# BadgeBoard.net
KiCad netlist of a schematic drawn in EAGLE
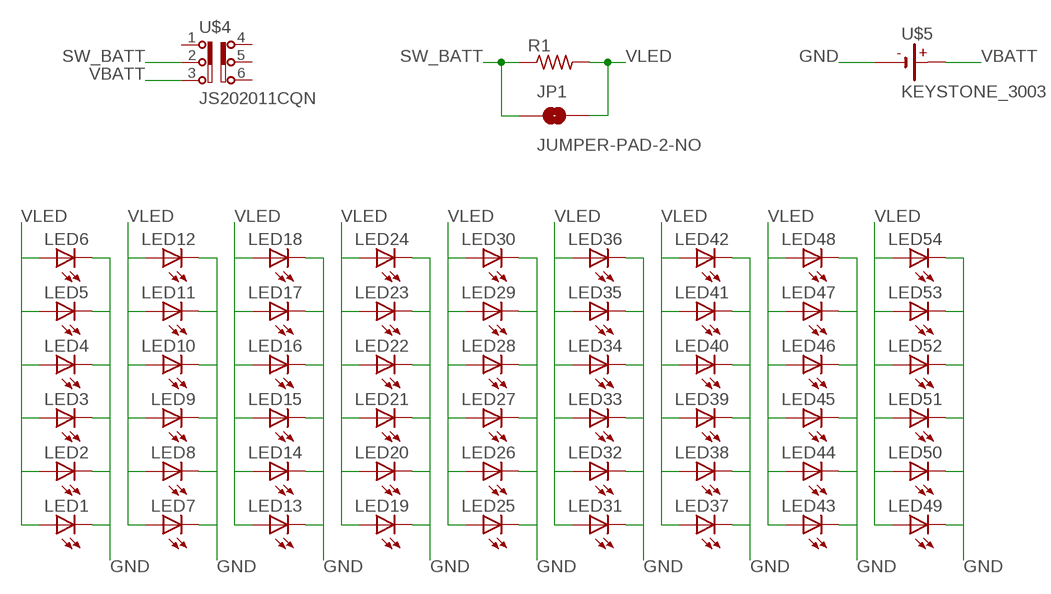
[diagram p0: schematic, sheet 1]

(export (version "E")
  (design (tool "Eeschema 10.0.6"))
  (components
    (comp (ref "JP1")
      (value "JUMPER-PAD-2-NO")
      (footprint "eagle-import:PAD-JUMPER-2-NO_NO_SILK")
      (libsource (lib "eagle-import") (part "JUMPER-PAD-2-NO"))
    )
    (comp (ref "LED1")
      (value "LED3MM")
      (footprint "eagle-import:LED3MM")
      (libsource (lib "eagle-import") (part "LED3MM"))
    )
    (comp (ref "LED2")
      (value "LED3MM")
      (footprint "eagle-import:LED3MM")
      (libsource (lib "eagle-import") (part "LED3MM"))
    )
    (comp (ref "LED3")
      (value "LED3MM")
      (footprint "eagle-import:LED3MM")
      (libsource (lib "eagle-import") (part "LED3MM"))
    )
    (comp (ref "LED4")
      (value "LED3MM")
      (footprint "eagle-import:LED3MM")
      (libsource (lib "eagle-import") (part "LED3MM"))
    )
    (comp (ref "LED5")
      (value "LED3MM")
      (footprint "eagle-import:LED3MM")
      (libsource (lib "eagle-import") (part "LED3MM"))
    )
    (comp (ref "LED6")
      (value "LED3MM")
      (footprint "eagle-import:LED3MM")
      (libsource (lib "eagle-import") (part "LED3MM"))
    )
    (comp (ref "LED7")
      (value "LED3MM")
      (footprint "eagle-import:LED3MM")
      (libsource (lib "eagle-import") (part "LED3MM"))
    )
    (comp (ref "LED8")
      (value "LED3MM")
      (footprint "eagle-import:LED3MM")
      (libsource (lib "eagle-import") (part "LED3MM"))
    )
    (comp (ref "LED9")
      (value "LED3MM")
      (footprint "eagle-import:LED3MM")
      (libsource (lib "eagle-import") (part "LED3MM"))
    )
    (comp (ref "LED10")
      (value "LED3MM")
      (footprint "eagle-import:LED3MM")
      (libsource (lib "eagle-import") (part "LED3MM"))
    )
    (comp (ref "LED11")
      (value "LED3MM")
      (footprint "eagle-import:LED3MM")
      (libsource (lib "eagle-import") (part "LED3MM"))
    )
    (comp (ref "LED12")
      (value "LED3MM")
      (footprint "eagle-import:LED3MM")
      (libsource (lib "eagle-import") (part "LED3MM"))
    )
    (comp (ref "LED13")
      (value "LED3MM")
      (footprint "eagle-import:LED3MM")
      (libsource (lib "eagle-import") (part "LED3MM"))
    )
    (comp (ref "LED14")
      (value "LED3MM")
      (footprint "eagle-import:LED3MM")
      (libsource (lib "eagle-import") (part "LED3MM"))
    )
    (comp (ref "LED15")
      (value "LED3MM")
      (footprint "eagle-import:LED3MM")
      (libsource (lib "eagle-import") (part "LED3MM"))
    )
    (comp (ref "LED16")
      (value "LED3MM")
      (footprint "eagle-import:LED3MM")
      (libsource (lib "eagle-import") (part "LED3MM"))
    )
    (comp (ref "LED17")
      (value "LED3MM")
      (footprint "eagle-import:LED3MM")
      (libsource (lib "eagle-import") (part "LED3MM"))
    )
    (comp (ref "LED18")
      (value "LED3MM")
      (footprint "eagle-import:LED3MM")
      (libsource (lib "eagle-import") (part "LED3MM"))
    )
    (comp (ref "LED19")
      (value "LED3MM")
      (footprint "eagle-import:LED3MM")
      (libsource (lib "eagle-import") (part "LED3MM"))
    )
    (comp (ref "LED20")
      (value "LED3MM")
      (footprint "eagle-import:LED3MM")
      (libsource (lib "eagle-import") (part "LED3MM"))
    )
    (comp (ref "LED21")
      (value "LED3MM")
      (footprint "eagle-import:LED3MM")
      (libsource (lib "eagle-import") (part "LED3MM"))
    )
    (comp (ref "LED22")
      (value "LED3MM")
      (footprint "eagle-import:LED3MM")
      (libsource (lib "eagle-import") (part "LED3MM"))
    )
    (comp (ref "LED23")
      (value "LED3MM")
      (footprint "eagle-import:LED3MM")
      (libsource (lib "eagle-import") (part "LED3MM"))
    )
    (comp (ref "LED24")
      (value "LED3MM")
      (footprint "eagle-import:LED3MM")
      (libsource (lib "eagle-import") (part "LED3MM"))
    )
    (comp (ref "LED25")
      (value "LED3MM")
      (footprint "eagle-import:LED3MM")
      (libsource (lib "eagle-import") (part "LED3MM"))
    )
    (comp (ref "LED26")
      (value "LED3MM")
      (footprint "eagle-import:LED3MM")
      (libsource (lib "eagle-import") (part "LED3MM"))
    )
    (comp (ref "LED27")
      (value "LED3MM")
      (footprint "eagle-import:LED3MM")
      (libsource (lib "eagle-import") (part "LED3MM"))
    )
    (comp (ref "LED28")
      (value "LED3MM")
      (footprint "eagle-import:LED3MM")
      (libsource (lib "eagle-import") (part "LED3MM"))
    )
    (comp (ref "LED29")
      (value "LED3MM")
      (footprint "eagle-import:LED3MM")
      (libsource (lib "eagle-import") (part "LED3MM"))
    )
    (comp (ref "LED30")
      (value "LED3MM")
      (footprint "eagle-import:LED3MM")
      (libsource (lib "eagle-import") (part "LED3MM"))
    )
    (comp (ref "LED31")
      (value "LED3MM")
      (footprint "eagle-import:LED3MM")
      (libsource (lib "eagle-import") (part "LED3MM"))
    )
    (comp (ref "LED32")
      (value "LED3MM")
      (footprint "eagle-import:LED3MM")
      (libsource (lib "eagle-import") (part "LED3MM"))
    )
    (comp (ref "LED33")
      (value "LED3MM")
      (footprint "eagle-import:LED3MM")
      (libsource (lib "eagle-import") (part "LED3MM"))
    )
    (comp (ref "LED34")
      (value "LED3MM")
      (footprint "eagle-import:LED3MM")
      (libsource (lib "eagle-import") (part "LED3MM"))
    )
    (comp (ref "LED35")
      (value "LED3MM")
      (footprint "eagle-import:LED3MM")
      (libsource (lib "eagle-import") (part "LED3MM"))
    )
    (comp (ref "LED36")
      (value "LED3MM")
      (footprint "eagle-import:LED3MM")
      (libsource (lib "eagle-import") (part "LED3MM"))
    )
    (comp (ref "LED37")
      (value "LED3MM")
      (footprint "eagle-import:LED3MM")
      (libsource (lib "eagle-import") (part "LED3MM"))
    )
    (comp (ref "LED38")
      (value "LED3MM")
      (footprint "eagle-import:LED3MM")
      (libsource (lib "eagle-import") (part "LED3MM"))
    )
    (comp (ref "LED39")
      (value "LED3MM")
      (footprint "eagle-import:LED3MM")
      (libsource (lib "eagle-import") (part "LED3MM"))
    )
    (comp (ref "LED40")
      (value "LED3MM")
      (footprint "eagle-import:LED3MM")
      (libsource (lib "eagle-import") (part "LED3MM"))
    )
    (comp (ref "LED41")
      (value "LED3MM")
      (footprint "eagle-import:LED3MM")
      (libsource (lib "eagle-import") (part "LED3MM"))
    )
    (comp (ref "LED42")
      (value "LED3MM")
      (footprint "eagle-import:LED3MM")
      (libsource (lib "eagle-import") (part "LED3MM"))
    )
    (comp (ref "LED43")
      (value "LED3MM")
      (footprint "eagle-import:LED3MM")
      (libsource (lib "eagle-import") (part "LED3MM"))
    )
    (comp (ref "LED44")
      (value "LED3MM")
      (footprint "eagle-import:LED3MM")
      (libsource (lib "eagle-import") (part "LED3MM"))
    )
    (comp (ref "LED45")
      (value "LED3MM")
      (footprint "eagle-import:LED3MM")
      (libsource (lib "eagle-import") (part "LED3MM"))
    )
    (comp (ref "LED46")
      (value "LED3MM")
      (footprint "eagle-import:LED3MM")
      (libsource (lib "eagle-import") (part "LED3MM"))
    )
    (comp (ref "LED47")
      (value "LED3MM")
      (footprint "eagle-import:LED3MM")
      (libsource (lib "eagle-import") (part "LED3MM"))
    )
    (comp (ref "LED48")
      (value "LED3MM")
      (footprint "eagle-import:LED3MM")
      (libsource (lib "eagle-import") (part "LED3MM"))
    )
    (comp (ref "LED49")
      (value "LED3MM")
      (footprint "eagle-import:LED3MM")
      (libsource (lib "eagle-import") (part "LED3MM"))
    )
    (comp (ref "LED50")
      (value "LED3MM")
      (footprint "eagle-import:LED3MM")
      (libsource (lib "eagle-import") (part "LED3MM"))
    )
    (comp (ref "LED51")
      (value "LED3MM")
      (footprint "eagle-import:LED3MM")
      (libsource (lib "eagle-import") (part "LED3MM"))
    )
    (comp (ref "LED52")
      (value "LED3MM")
      (footprint "eagle-import:LED3MM")
      (libsource (lib "eagle-import") (part "LED3MM"))
    )
    (comp (ref "LED53")
      (value "LED3MM")
      (footprint "eagle-import:LED3MM")
      (libsource (lib "eagle-import") (part "LED3MM"))
    )
    (comp (ref "LED54")
      (value "LED3MM")
      (footprint "eagle-import:LED3MM")
      (libsource (lib "eagle-import") (part "LED3MM"))
    )
    (comp (ref "R1")
      (value "R-US_0207/9")
      (footprint "eagle-import:0207_9")
      (libsource (lib "eagle-import") (part "R-US_0207/9"))
    )
    (comp (ref "U$4")
      (value "JS202011CQN")
      (footprint "eagle-import:JS202011CQN")
      (libsource (lib "eagle-import") (part "JS202011CQN"))
    )
    (comp (ref "U$5")
      (value "KEYSTONE_3003")
      (footprint "eagle-import:KEYSTONE_3003")
      (libsource (lib "eagle-import") (part "KEYSTONE_3003"))
    )
  )
  (nets
    (net (code "1") (name "/GND") (class "Default")
      (node (ref "LED1") (pin "K") (pinfunction "C_K") (pintype "passive"))
      (node (ref "LED10") (pin "K") (pinfunction "C_K") (pintype "passive"))
      (node (ref "LED11") (pin "K") (pinfunction "C_K") (pintype "passive"))
      (node (ref "LED12") (pin "K") (pinfunction "C_K") (pintype "passive"))
      (node (ref "LED13") (pin "K") (pinfunction "C_K") (pintype "passive"))
      (node (ref "LED14") (pin "K") (pinfunction "C_K") (pintype "passive"))
      (node (ref "LED15") (pin "K") (pinfunction "C_K") (pintype "passive"))
      (node (ref "LED16") (pin "K") (pinfunction "C_K") (pintype "passive"))
      (node (ref "LED17") (pin "K") (pinfunction "C_K") (pintype "passive"))
      (node (ref "LED18") (pin "K") (pinfunction "C_K") (pintype "passive"))
      (node (ref "LED19") (pin "K") (pinfunction "C_K") (pintype "passive"))
      (node (ref "LED2") (pin "K") (pinfunction "C_K") (pintype "passive"))
      (node (ref "LED20") (pin "K") (pinfunction "C_K") (pintype "passive"))
      (node (ref "LED21") (pin "K") (pinfunction "C_K") (pintype "passive"))
      (node (ref "LED22") (pin "K") (pinfunction "C_K") (pintype "passive"))
      (node (ref "LED23") (pin "K") (pinfunction "C_K") (pintype "passive"))
      (node (ref "LED24") (pin "K") (pinfunction "C_K") (pintype "passive"))
      (node (ref "LED25") (pin "K") (pinfunction "C_K") (pintype "passive"))
      (node (ref "LED26") (pin "K") (pinfunction "C_K") (pintype "passive"))
      (node (ref "LED27") (pin "K") (pinfunction "C_K") (pintype "passive"))
      (node (ref "LED28") (pin "K") (pinfunction "C_K") (pintype "passive"))
      (node (ref "LED29") (pin "K") (pinfunction "C_K") (pintype "passive"))
      (node (ref "LED3") (pin "K") (pinfunction "C_K") (pintype "passive"))
      (node (ref "LED30") (pin "K") (pinfunction "C_K") (pintype "passive"))
      (node (ref "LED31") (pin "K") (pinfunction "C_K") (pintype "passive"))
      (node (ref "LED32") (pin "K") (pinfunction "C_K") (pintype "passive"))
      (node (ref "LED33") (pin "K") (pinfunction "C_K") (pintype "passive"))
      (node (ref "LED34") (pin "K") (pinfunction "C_K") (pintype "passive"))
      (node (ref "LED35") (pin "K") (pinfunction "C_K") (pintype "passive"))
      (node (ref "LED36") (pin "K") (pinfunction "C_K") (pintype "passive"))
      (node (ref "LED37") (pin "K") (pinfunction "C_K") (pintype "passive"))
      (node (ref "LED38") (pin "K") (pinfunction "C_K") (pintype "passive"))
      (node (ref "LED39") (pin "K") (pinfunction "C_K") (pintype "passive"))
      (node (ref "LED4") (pin "K") (pinfunction "C_K") (pintype "passive"))
      (node (ref "LED40") (pin "K") (pinfunction "C_K") (pintype "passive"))
      (node (ref "LED41") (pin "K") (pinfunction "C_K") (pintype "passive"))
      (node (ref "LED42") (pin "K") (pinfunction "C_K") (pintype "passive"))
      (node (ref "LED43") (pin "K") (pinfunction "C_K") (pintype "passive"))
      (node (ref "LED44") (pin "K") (pinfunction "C_K") (pintype "passive"))
      (node (ref "LED45") (pin "K") (pinfunction "C_K") (pintype "passive"))
      (node (ref "LED46") (pin "K") (pinfunction "C_K") (pintype "passive"))
      (node (ref "LED47") (pin "K") (pinfunction "C_K") (pintype "passive"))
      (node (ref "LED48") (pin "K") (pinfunction "C_K") (pintype "passive"))
      (node (ref "LED49") (pin "K") (pinfunction "C_K") (pintype "passive"))
      (node (ref "LED5") (pin "K") (pinfunction "C_K") (pintype "passive"))
      (node (ref "LED50") (pin "K") (pinfunction "C_K") (pintype "passive"))
      (node (ref "LED51") (pin "K") (pinfunction "C_K") (pintype "passive"))
      (node (ref "LED52") (pin "K") (pinfunction "C_K") (pintype "passive"))
      (node (ref "LED53") (pin "K") (pinfunction "C_K") (pintype "passive"))
      (node (ref "LED54") (pin "K") (pinfunction "C_K") (pintype "passive"))
      (node (ref "LED6") (pin "K") (pinfunction "C_K") (pintype "passive"))
      (node (ref "LED7") (pin "K") (pinfunction "C_K") (pintype "passive"))
      (node (ref "LED8") (pin "K") (pinfunction "C_K") (pintype "passive"))
      (node (ref "LED9") (pin "K") (pinfunction "C_K") (pintype "passive"))
      (node (ref "U$5") (pin "P$3") (pinfunction "-_P$3") (pintype "passive"))
    )
    (net (code "2") (name "/SW_BATT") (class "Default")
      (node (ref "JP1") (pin "1") (pinfunction "1_1") (pintype "passive"))
      (node (ref "R1") (pin "1") (pinfunction "1_1") (pintype "passive"))
      (node (ref "U$4") (pin "2") (pinfunction "2_2") (pintype "passive"))
    )
    (net (code "3") (name "/VBATT") (class "Default")
      (node (ref "U$4") (pin "3") (pinfunction "3_3") (pintype "passive"))
      (node (ref "U$5") (pin "P$1") (pinfunction "+_P$1") (pintype "passive"))
      (node (ref "U$5") (pin "P$2") (pinfunction "+_P$2") (pintype "passive"))
    )
    (net (code "4") (name "/VLED") (class "Default")
      (node (ref "JP1") (pin "2") (pinfunction "2_2") (pintype "passive"))
      (node (ref "LED1") (pin "A") (pinfunction "A_A") (pintype "passive"))
      (node (ref "LED10") (pin "A") (pinfunction "A_A") (pintype "passive"))
      (node (ref "LED11") (pin "A") (pinfunction "A_A") (pintype "passive"))
      (node (ref "LED12") (pin "A") (pinfunction "A_A") (pintype "passive"))
      (node (ref "LED13") (pin "A") (pinfunction "A_A") (pintype "passive"))
      (node (ref "LED14") (pin "A") (pinfunction "A_A") (pintype "passive"))
      (node (ref "LED15") (pin "A") (pinfunction "A_A") (pintype "passive"))
      (node (ref "LED16") (pin "A") (pinfunction "A_A") (pintype "passive"))
      (node (ref "LED17") (pin "A") (pinfunction "A_A") (pintype "passive"))
      (node (ref "LED18") (pin "A") (pinfunction "A_A") (pintype "passive"))
      (node (ref "LED19") (pin "A") (pinfunction "A_A") (pintype "passive"))
      (node (ref "LED2") (pin "A") (pinfunction "A_A") (pintype "passive"))
      (node (ref "LED20") (pin "A") (pinfunction "A_A") (pintype "passive"))
      (node (ref "LED21") (pin "A") (pinfunction "A_A") (pintype "passive"))
      (node (ref "LED22") (pin "A") (pinfunction "A_A") (pintype "passive"))
      (node (ref "LED23") (pin "A") (pinfunction "A_A") (pintype "passive"))
      (node (ref "LED24") (pin "A") (pinfunction "A_A") (pintype "passive"))
      (node (ref "LED25") (pin "A") (pinfunction "A_A") (pintype "passive"))
      (node (ref "LED26") (pin "A") (pinfunction "A_A") (pintype "passive"))
      (node (ref "LED27") (pin "A") (pinfunction "A_A") (pintype "passive"))
      (node (ref "LED28") (pin "A") (pinfunction "A_A") (pintype "passive"))
      (node (ref "LED29") (pin "A") (pinfunction "A_A") (pintype "passive"))
      (node (ref "LED3") (pin "A") (pinfunction "A_A") (pintype "passive"))
      (node (ref "LED30") (pin "A") (pinfunction "A_A") (pintype "passive"))
      (node (ref "LED31") (pin "A") (pinfunction "A_A") (pintype "passive"))
      (node (ref "LED32") (pin "A") (pinfunction "A_A") (pintype "passive"))
      (node (ref "LED33") (pin "A") (pinfunction "A_A") (pintype "passive"))
      (node (ref "LED34") (pin "A") (pinfunction "A_A") (pintype "passive"))
      (node (ref "LED35") (pin "A") (pinfunction "A_A") (pintype "passive"))
      (node (ref "LED36") (pin "A") (pinfunction "A_A") (pintype "passive"))
      (node (ref "LED37") (pin "A") (pinfunction "A_A") (pintype "passive"))
      (node (ref "LED38") (pin "A") (pinfunction "A_A") (pintype "passive"))
      (node (ref "LED39") (pin "A") (pinfunction "A_A") (pintype "passive"))
      (node (ref "LED4") (pin "A") (pinfunction "A_A") (pintype "passive"))
      (node (ref "LED40") (pin "A") (pinfunction "A_A") (pintype "passive"))
      (node (ref "LED41") (pin "A") (pinfunction "A_A") (pintype "passive"))
      (node (ref "LED42") (pin "A") (pinfunction "A_A") (pintype "passive"))
      (node (ref "LED43") (pin "A") (pinfunction "A_A") (pintype "passive"))
      (node (ref "LED44") (pin "A") (pinfunction "A_A") (pintype "passive"))
      (node (ref "LED45") (pin "A") (pinfunction "A_A") (pintype "passive"))
      (node (ref "LED46") (pin "A") (pinfunction "A_A") (pintype "passive"))
      (node (ref "LED47") (pin "A") (pinfunction "A_A") (pintype "passive"))
      (node (ref "LED48") (pin "A") (pinfunction "A_A") (pintype "passive"))
      (node (ref "LED49") (pin "A") (pinfunction "A_A") (pintype "passive"))
      (node (ref "LED5") (pin "A") (pinfunction "A_A") (pintype "passive"))
      (node (ref "LED50") (pin "A") (pinfunction "A_A") (pintype "passive"))
      (node (ref "LED51") (pin "A") (pinfunction "A_A") (pintype "passive"))
      (node (ref "LED52") (pin "A") (pinfunction "A_A") (pintype "passive"))
      (node (ref "LED53") (pin "A") (pinfunction "A_A") (pintype "passive"))
      (node (ref "LED54") (pin "A") (pinfunction "A_A") (pintype "passive"))
      (node (ref "LED6") (pin "A") (pinfunction "A_A") (pintype "passive"))
      (node (ref "LED7") (pin "A") (pinfunction "A_A") (pintype "passive"))
      (node (ref "LED8") (pin "A") (pinfunction "A_A") (pintype "passive"))
      (node (ref "LED9") (pin "A") (pinfunction "A_A") (pintype "passive"))
      (node (ref "R1") (pin "2") (pinfunction "2_2") (pintype "passive"))
    )
    (net (code "5") (name "unconnected-(U$4-Pad1)") (class "Default")
      (node (ref "U$4") (pin "1") (pinfunction "1_1") (pintype "passive"))
    )
    (net (code "6") (name "unconnected-(U$4-Pad4)") (class "Default")
      (node (ref "U$4") (pin "4") (pinfunction "4_4") (pintype "passive"))
    )
    (net (code "7") (name "unconnected-(U$4-Pad5)") (class "Default")
      (node (ref "U$4") (pin "5") (pinfunction "5_5") (pintype "passive"))
    )
    (net (code "8") (name "unconnected-(U$4-Pad6)") (class "Default")
      (node (ref "U$4") (pin "6") (pinfunction "6_6") (pintype "passive"))
    )
  )
)
